# I2C-AD4DA.net
KiCad netlist of a schematic drawn in EAGLE
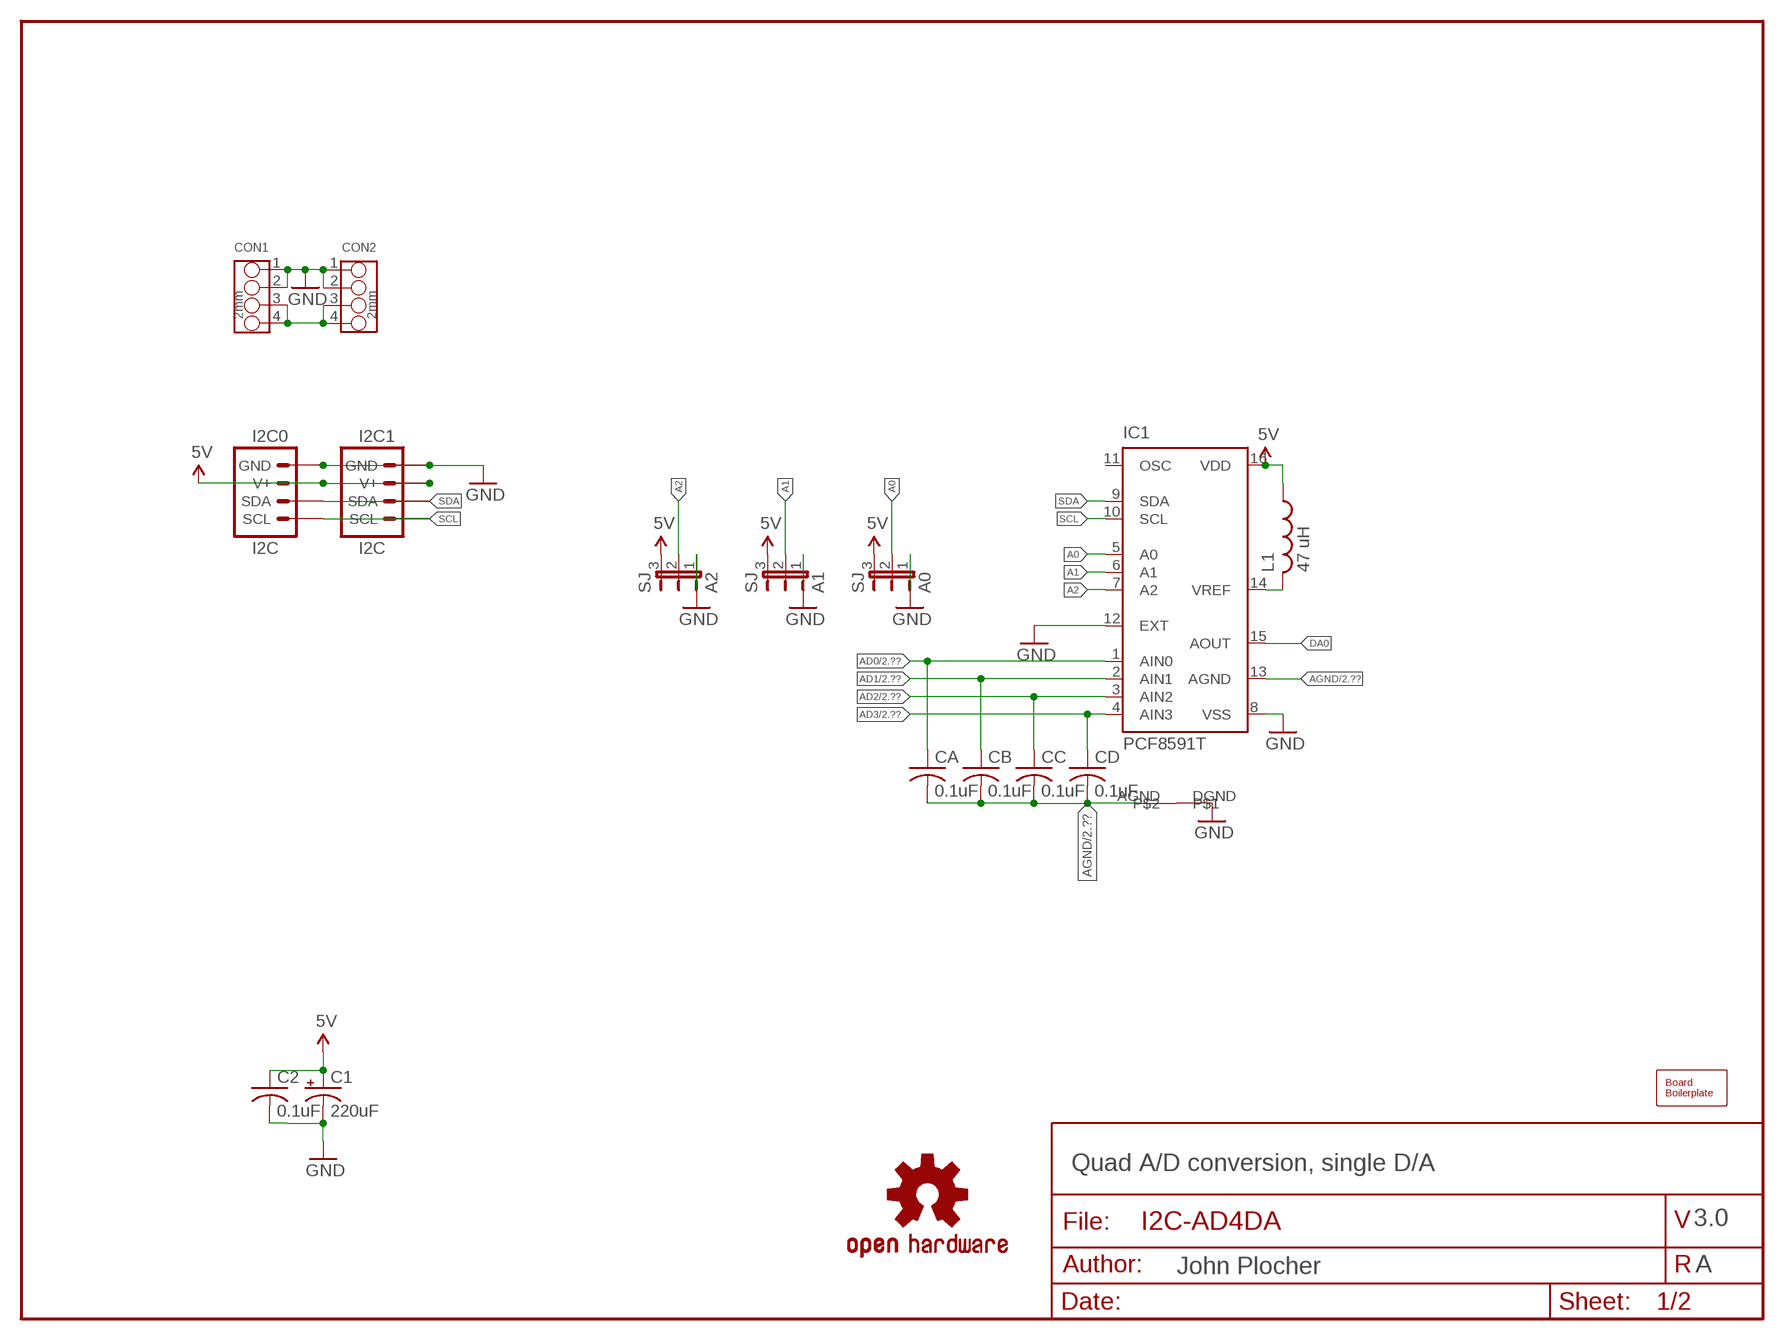
[diagram p0: schematic, sheet 1]
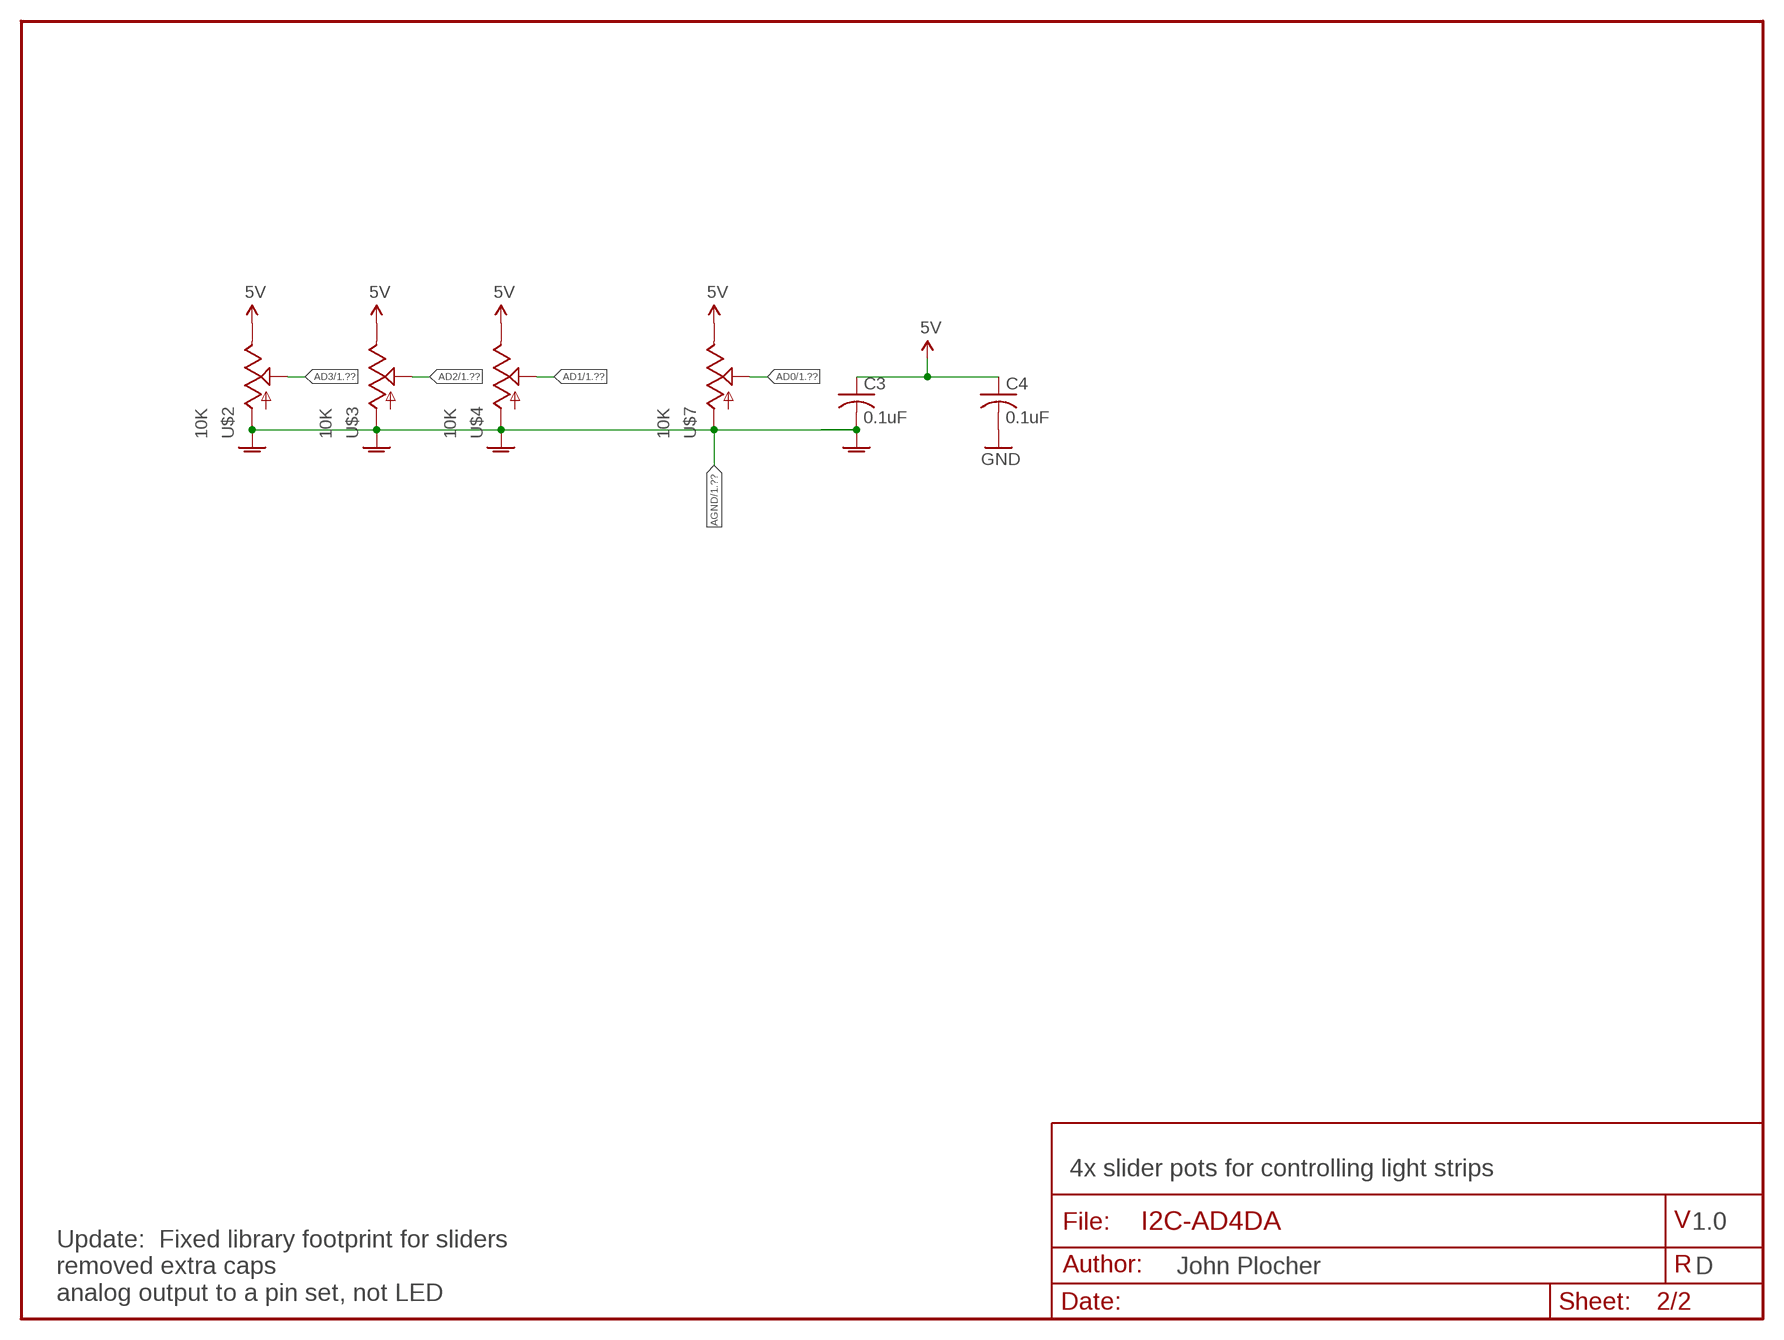
[diagram p1: schematic, sheet 2]

(export (version "E")
  (design (tool "Eeschema 10.0.6"))
  (components
    (comp (ref "C3")
      (value "0.1uF")
      (footprint "eagle-import:0805-CAP")
      (libsource (lib "eagle-import") (part "CAP0805"))
    )
    (comp (ref "C4")
      (value "0.1uF")
      (footprint "eagle-import:0805-CAP")
      (libsource (lib "eagle-import") (part "CAP0805"))
    )
    (comp (ref "U$2")
      (value "10K")
      (footprint "eagle-import:SLIDER-45MM")
      (libsource (lib "eagle-import") (part "R-SLIDE-POT-45MM"))
    )
    (comp (ref "U$3")
      (value "10K")
      (footprint "eagle-import:SLIDER-45MM")
      (libsource (lib "eagle-import") (part "R-SLIDE-POT-45MM"))
    )
    (comp (ref "U$4")
      (value "10K")
      (footprint "eagle-import:SLIDER-45MM")
      (libsource (lib "eagle-import") (part "R-SLIDE-POT-45MM"))
    )
    (comp (ref "U$7")
      (value "10K")
      (footprint "eagle-import:SLIDER-45MM")
      (libsource (lib "eagle-import") (part "R-SLIDE-POT-45MM"))
    )
    (comp (ref "A0")
      (value "SJ")
      (footprint "eagle-import:SJ_3_PASTE1&2")
      (libsource (lib "eagle-import") (part "JUMPER-31-2"))
    )
    (comp (ref "A1")
      (value "SJ")
      (footprint "eagle-import:SJ_3_PASTE1&2")
      (libsource (lib "eagle-import") (part "JUMPER-31-2"))
    )
    (comp (ref "A2")
      (value "SJ")
      (footprint "eagle-import:SJ_3_PASTE1&2")
      (libsource (lib "eagle-import") (part "JUMPER-31-2"))
    )
    (comp (ref "BOARD1")
      (value "BOARD")
      (footprint "eagle-import:BOARD-DINRAIL-3.17INX10CM")
      (libsource (lib "eagle-import") (part "BOARD80X100"))
    )
    (comp (ref "C1")
      (value "220uF")
      (footprint "eagle-import:0810-CAP")
      (libsource (lib "eagle-import") (part "CAP-POL0810"))
    )
    (comp (ref "C2")
      (value "0.1uF")
      (footprint "eagle-import:0805-CAP")
      (libsource (lib "eagle-import") (part "CAP0805"))
    )
    (comp (ref "CA")
      (value "0.1uF")
      (footprint "eagle-import:0805-CAP")
      (libsource (lib "eagle-import") (part "CAP0805"))
    )
    (comp (ref "CB")
      (value "0.1uF")
      (footprint "eagle-import:0805-CAP")
      (libsource (lib "eagle-import") (part "CAP0805"))
    )
    (comp (ref "CC")
      (value "0.1uF")
      (footprint "eagle-import:0805-CAP")
      (libsource (lib "eagle-import") (part "CAP0805"))
    )
    (comp (ref "CD")
      (value "0.1uF")
      (footprint "eagle-import:0805-CAP")
      (libsource (lib "eagle-import") (part "CAP0805"))
    )
    (comp (ref "CON1")
      (value "2mm")
      (footprint "eagle-import:4P-2.0")
      (libsource (lib "eagle-import") (part "CONNECTOR-GROVE-4P-2.0-3470130P1"))
    )
    (comp (ref "CON2")
      (value "2mm")
      (footprint "eagle-import:4P-2.0")
      (libsource (lib "eagle-import") (part "CONNECTOR-GROVE-4P-2.0-3470130P1"))
    )
    (comp (ref "I2C0")
      (value "I2C")
      (footprint "eagle-import:I2C-L")
      (libsource (lib "eagle-import") (part "CONNECTOR-I2CLEFT"))
    )
    (comp (ref "I2C1")
      (value "I2C")
      (footprint "eagle-import:I2C-L")
      (libsource (lib "eagle-import") (part "CONNECTOR-I2CLEFT"))
    )
    (comp (ref "IC1")
      (value "PCF8591T")
      (footprint "eagle-import:SO16W")
      (fields (field (name "MPN") "PCF8591T/2,512"))
      (libsource (lib "eagle-import") (part "PCF8591T"))
    )
    (comp (ref "L1")
      (value "47 uH")
      (footprint "eagle-import:L2012C")
      (libsource (lib "eagle-import") (part "L-USL2012C"))
    )
    (comp (ref "LOGO1")
      (value "OSHW")
      (footprint "eagle-import:OSHW-LOGO-L")
      (libsource (lib "eagle-import") (part "DOC-OSHW-LOGO-L"))
    )
    (comp (ref "U$1")
      (value "AGND+DGND")
      (footprint "eagle-import:AGND+DGND")
      (libsource (lib "eagle-import") (part "AGND+DGND"))
    )
  )
  (nets
    (net (code "1") (name "5V") (class "Default")
      (node (ref "A0") (pin "3") (pinfunction "3_3") (pintype "passive"))
      (node (ref "A1") (pin "3") (pinfunction "3_3") (pintype "passive"))
      (node (ref "A2") (pin "3") (pinfunction "3_3") (pintype "passive"))
      (node (ref "C1") (pin "+") (pinfunction "+_+") (pintype "passive"))
      (node (ref "C2") (pin "1") (pinfunction "1_1") (pintype "passive"))
      (node (ref "C3") (pin "1") (pinfunction "1_1") (pintype "passive"))
      (node (ref "C4") (pin "1") (pinfunction "1_1") (pintype "passive"))
      (node (ref "I2C0") (pin "V+") (pinfunction "V+_V+") (pintype "passive"))
      (node (ref "I2C0") (pin "V+@1") (pinfunction "V+_V+@1") (pintype "passive"))
      (node (ref "I2C1") (pin "V+") (pinfunction "V+_V+") (pintype "passive"))
      (node (ref "I2C1") (pin "V+@1") (pinfunction "V+_V+@1") (pintype "passive"))
      (node (ref "IC1") (pin "16") (pinfunction "VDD_16") (pintype "power_in"))
      (node (ref "L1") (pin "1") (pinfunction "1_1") (pintype "passive"))
      (node (ref "U$2") (pin "E") (pinfunction "E_E") (pintype "passive"))
      (node (ref "U$3") (pin "E") (pinfunction "E_E") (pintype "passive"))
      (node (ref "U$4") (pin "E") (pinfunction "E_E") (pintype "passive"))
      (node (ref "U$7") (pin "E") (pinfunction "E_E") (pintype "passive"))
    )
    (net (code "2") (name "A0") (class "Default")
      (node (ref "A0") (pin "2") (pinfunction "2_2") (pintype "passive"))
      (node (ref "IC1") (pin "5") (pinfunction "A0_5") (pintype "input"))
    )
    (net (code "3") (name "A1") (class "Default")
      (node (ref "A1") (pin "2") (pinfunction "2_2") (pintype "passive"))
      (node (ref "IC1") (pin "6") (pinfunction "A1_6") (pintype "input"))
    )
    (net (code "4") (name "A2") (class "Default")
      (node (ref "A2") (pin "2") (pinfunction "2_2") (pintype "passive"))
      (node (ref "IC1") (pin "7") (pinfunction "A2_7") (pintype "input"))
    )
    (net (code "5") (name "AD0") (class "Default")
      (node (ref "CA") (pin "1") (pinfunction "1_1") (pintype "passive"))
      (node (ref "IC1") (pin "1") (pinfunction "AIN0_1") (pintype "input"))
      (node (ref "U$7") (pin "S") (pinfunction "S_S") (pintype "passive"))
    )
    (net (code "6") (name "AD1") (class "Default")
      (node (ref "CB") (pin "1") (pinfunction "1_1") (pintype "passive"))
      (node (ref "IC1") (pin "2") (pinfunction "AIN1_2") (pintype "input"))
      (node (ref "U$4") (pin "S") (pinfunction "S_S") (pintype "passive"))
    )
    (net (code "7") (name "AD2") (class "Default")
      (node (ref "CC") (pin "1") (pinfunction "1_1") (pintype "passive"))
      (node (ref "IC1") (pin "3") (pinfunction "AIN2_3") (pintype "input"))
      (node (ref "U$3") (pin "S") (pinfunction "S_S") (pintype "passive"))
    )
    (net (code "8") (name "AD3") (class "Default")
      (node (ref "CD") (pin "1") (pinfunction "1_1") (pintype "passive"))
      (node (ref "IC1") (pin "4") (pinfunction "AIN3_4") (pintype "input"))
      (node (ref "U$2") (pin "S") (pinfunction "S_S") (pintype "passive"))
    )
    (net (code "9") (name "AGND") (class "Default")
      (node (ref "C3") (pin "2") (pinfunction "2_2") (pintype "passive"))
      (node (ref "CA") (pin "2") (pinfunction "2_2") (pintype "passive"))
      (node (ref "CB") (pin "2") (pinfunction "2_2") (pintype "passive"))
      (node (ref "CC") (pin "2") (pinfunction "2_2") (pintype "passive"))
      (node (ref "CD") (pin "2") (pinfunction "2_2") (pintype "passive"))
      (node (ref "IC1") (pin "13") (pinfunction "AGND_13") (pintype "power_in"))
      (node (ref "U$1") (pin "AGND") (pinfunction "P$1_AGND") (pintype "bidirectional"))
      (node (ref "U$2") (pin "A") (pinfunction "A_A") (pintype "passive"))
      (node (ref "U$2") (pin "AGND@0") (pinfunction "AGND_AGND@0") (pintype "power_in"))
      (node (ref "U$2") (pin "AGND@1") (pinfunction "AGND_AGND@1") (pintype "power_in"))
      (node (ref "U$3") (pin "A") (pinfunction "A_A") (pintype "passive"))
      (node (ref "U$3") (pin "AGND@0") (pinfunction "AGND_AGND@0") (pintype "power_in"))
      (node (ref "U$3") (pin "AGND@1") (pinfunction "AGND_AGND@1") (pintype "power_in"))
      (node (ref "U$4") (pin "A") (pinfunction "A_A") (pintype "passive"))
      (node (ref "U$4") (pin "AGND@0") (pinfunction "AGND_AGND@0") (pintype "power_in"))
      (node (ref "U$4") (pin "AGND@1") (pinfunction "AGND_AGND@1") (pintype "power_in"))
      (node (ref "U$7") (pin "A") (pinfunction "A_A") (pintype "passive"))
      (node (ref "U$7") (pin "AGND@0") (pinfunction "AGND_AGND@0") (pintype "power_in"))
      (node (ref "U$7") (pin "AGND@1") (pinfunction "AGND_AGND@1") (pintype "power_in"))
    )
    (net (code "10") (name "DA0") (class "Default")
      (node (ref "IC1") (pin "15") (pinfunction "AOUT_15") (pintype "output"))
    )
    (net (code "11") (name "GND") (class "Default")
      (node (ref "A0") (pin "1") (pinfunction "1_1") (pintype "passive"))
      (node (ref "A1") (pin "1") (pinfunction "1_1") (pintype "passive"))
      (node (ref "A2") (pin "1") (pinfunction "1_1") (pintype "passive"))
      (node (ref "C1") (pin "-") (pinfunction "-_-") (pintype "passive"))
      (node (ref "C2") (pin "2") (pinfunction "2_2") (pintype "passive"))
      (node (ref "C4") (pin "2") (pinfunction "2_2") (pintype "passive"))
      (node (ref "CON1") (pin "1") (pinfunction "1_1") (pintype "bidirectional"))
      (node (ref "CON1") (pin "2") (pinfunction "2_2") (pintype "bidirectional"))
      (node (ref "CON2") (pin "1") (pinfunction "1_1") (pintype "bidirectional"))
      (node (ref "CON2") (pin "2") (pinfunction "2_2") (pintype "bidirectional"))
      (node (ref "I2C0") (pin "GND") (pinfunction "GND_GND") (pintype "passive"))
      (node (ref "I2C0") (pin "GND@1") (pinfunction "GND_GND@1") (pintype "passive"))
      (node (ref "I2C1") (pin "GND") (pinfunction "GND_GND") (pintype "passive"))
      (node (ref "I2C1") (pin "GND@1") (pinfunction "GND_GND@1") (pintype "passive"))
      (node (ref "IC1") (pin "12") (pinfunction "EXT_12") (pintype "input"))
      (node (ref "IC1") (pin "8") (pinfunction "VSS_8") (pintype "power_in"))
      (node (ref "U$1") (pin "DGND") (pinfunction "P$2_DGND") (pintype "bidirectional"))
    )
    (net (code "12") (name "Net-(CON1-Pad3)") (class "Default")
      (node (ref "CON1") (pin "3") (pinfunction "3_3") (pintype "bidirectional"))
      (node (ref "CON1") (pin "4") (pinfunction "4_4") (pintype "bidirectional"))
      (node (ref "CON2") (pin "3") (pinfunction "3_3") (pintype "bidirectional"))
      (node (ref "CON2") (pin "4") (pinfunction "4_4") (pintype "bidirectional"))
    )
    (net (code "13") (name "Net-(IC1-VREF)") (class "Default")
      (node (ref "IC1") (pin "14") (pinfunction "VREF_14") (pintype "input"))
      (node (ref "L1") (pin "2") (pinfunction "2_2") (pintype "passive"))
    )
    (net (code "14") (name "SCL") (class "Default")
      (node (ref "I2C0") (pin "SCL") (pinfunction "SCL_SCL") (pintype "passive"))
      (node (ref "I2C0") (pin "SCL@1") (pinfunction "SCL_SCL@1") (pintype "passive"))
      (node (ref "I2C1") (pin "SCL") (pinfunction "SCL_SCL") (pintype "passive"))
      (node (ref "I2C1") (pin "SCL@1") (pinfunction "SCL_SCL@1") (pintype "passive"))
      (node (ref "IC1") (pin "10") (pinfunction "SCL_10") (pintype "input"))
    )
    (net (code "15") (name "SDA") (class "Default")
      (node (ref "I2C0") (pin "SDA") (pinfunction "SDA_SDA") (pintype "passive"))
      (node (ref "I2C0") (pin "SDA@1") (pinfunction "SDA_SDA@1") (pintype "passive"))
      (node (ref "I2C1") (pin "SDA") (pinfunction "SDA_SDA") (pintype "passive"))
      (node (ref "I2C1") (pin "SDA@1") (pinfunction "SDA_SDA@1") (pintype "passive"))
      (node (ref "IC1") (pin "9") (pinfunction "SDA_9") (pintype "bidirectional"))
    )
    (net (code "16") (name "unconnected-(IC1-OSC-Pad11)") (class "Default")
      (node (ref "IC1") (pin "11") (pinfunction "OSC_11") (pintype "input"))
    )
  )
)
